# CP_Watsonville_Mid-Model.net
KiCad netlist of a schematic drawn in EAGLE
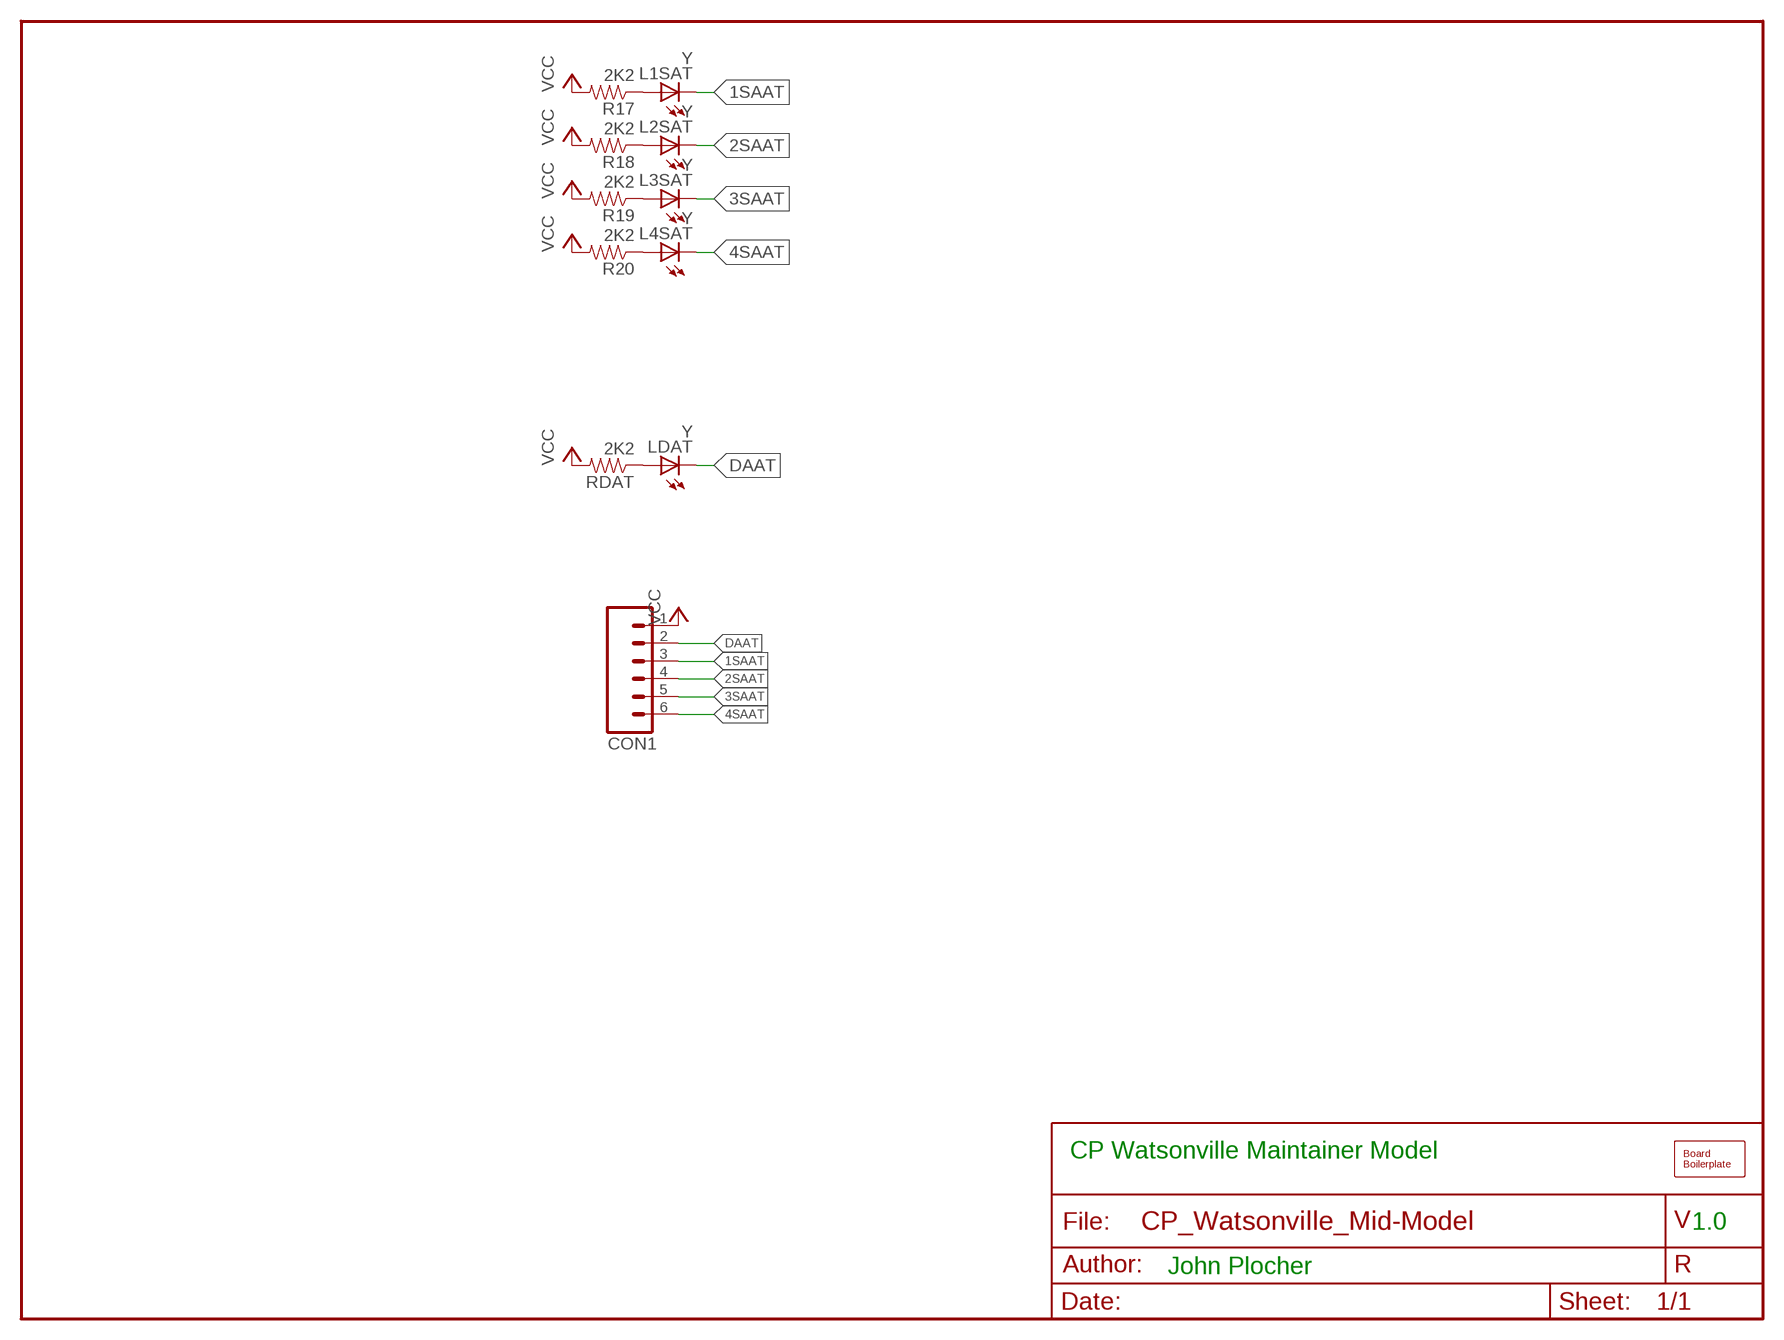
[diagram p0: schematic, sheet 1]

(export (version "E")
  (design (tool "Eeschema 10.0.6"))
  (components
    (comp (ref "BOARD1")
      (value "BOARD100X100")
      (footprint "eagle-import:BOARD-SEEED10X10")
      (libsource (lib "eagle-import") (part "BOARD100X100"))
    )
    (comp (ref "CON1")
      (value "CONNECTOR-M06LOCK")
      (footprint "eagle-import:1X06_LOCK")
      (libsource (lib "eagle-import") (part "CONNECTOR-M06LOCK"))
    )
    (comp (ref "L1SAT")
      (value "Y")
      (footprint "eagle-import:0603-LED")
      (libsource (lib "eagle-import") (part "LED0603-LED"))
    )
    (comp (ref "L2SAT")
      (value "Y")
      (footprint "eagle-import:0603-LED")
      (libsource (lib "eagle-import") (part "LED0603-LED"))
    )
    (comp (ref "L3SAT")
      (value "Y")
      (footprint "eagle-import:0603-LED")
      (libsource (lib "eagle-import") (part "LED0603-LED"))
    )
    (comp (ref "L4SAT")
      (value "Y")
      (footprint "eagle-import:0603-LED")
      (libsource (lib "eagle-import") (part "LED0603-LED"))
    )
    (comp (ref "LDAT")
      (value "Y")
      (footprint "eagle-import:0603-LED")
      (libsource (lib "eagle-import") (part "LED0603-LED"))
    )
    (comp (ref "R17")
      (value "2K2")
      (footprint "eagle-import:0603-RES")
      (libsource (lib "eagle-import") (part "R0603-RES"))
    )
    (comp (ref "R18")
      (value "2K2")
      (footprint "eagle-import:0603-RES")
      (libsource (lib "eagle-import") (part "R0603-RES"))
    )
    (comp (ref "R19")
      (value "2K2")
      (footprint "eagle-import:0603-RES")
      (libsource (lib "eagle-import") (part "R0603-RES"))
    )
    (comp (ref "R20")
      (value "2K2")
      (footprint "eagle-import:0603-RES")
      (libsource (lib "eagle-import") (part "R0603-RES"))
    )
    (comp (ref "RDAT")
      (value "2K2")
      (footprint "eagle-import:0603-RES")
      (libsource (lib "eagle-import") (part "R0603-RES"))
    )
  )
  (nets
    (net (code "1") (name "1SAAT") (class "Default")
      (node (ref "CON1") (pin "3") (pinfunction "3_3") (pintype "passive"))
      (node (ref "L1SAT") (pin "C") (pinfunction "C_C") (pintype "passive"))
    )
    (net (code "2") (name "2SAAT") (class "Default")
      (node (ref "CON1") (pin "4") (pinfunction "4_4") (pintype "passive"))
      (node (ref "L2SAT") (pin "C") (pinfunction "C_C") (pintype "passive"))
    )
    (net (code "3") (name "3SAAT") (class "Default")
      (node (ref "CON1") (pin "5") (pinfunction "5_5") (pintype "passive"))
      (node (ref "L3SAT") (pin "C") (pinfunction "C_C") (pintype "passive"))
    )
    (net (code "4") (name "4SAAT") (class "Default")
      (node (ref "CON1") (pin "6") (pinfunction "6_6") (pintype "passive"))
      (node (ref "L4SAT") (pin "C") (pinfunction "C_C") (pintype "passive"))
    )
    (net (code "5") (name "DAAT") (class "Default")
      (node (ref "CON1") (pin "2") (pinfunction "2_2") (pintype "passive"))
      (node (ref "LDAT") (pin "C") (pinfunction "C_C") (pintype "passive"))
    )
    (net (code "6") (name "Net-(L1SAT-PadA)") (class "Default")
      (node (ref "L1SAT") (pin "A") (pinfunction "A_A") (pintype "passive"))
      (node (ref "R17") (pin "1") (pinfunction "1_1") (pintype "passive"))
    )
    (net (code "7") (name "Net-(L2SAT-PadA)") (class "Default")
      (node (ref "L2SAT") (pin "A") (pinfunction "A_A") (pintype "passive"))
      (node (ref "R18") (pin "1") (pinfunction "1_1") (pintype "passive"))
    )
    (net (code "8") (name "Net-(L3SAT-PadA)") (class "Default")
      (node (ref "L3SAT") (pin "A") (pinfunction "A_A") (pintype "passive"))
      (node (ref "R19") (pin "1") (pinfunction "1_1") (pintype "passive"))
    )
    (net (code "9") (name "Net-(L4SAT-PadA)") (class "Default")
      (node (ref "L4SAT") (pin "A") (pinfunction "A_A") (pintype "passive"))
      (node (ref "R20") (pin "1") (pinfunction "1_1") (pintype "passive"))
    )
    (net (code "10") (name "Net-(LDAT-PadA)") (class "Default")
      (node (ref "LDAT") (pin "A") (pinfunction "A_A") (pintype "passive"))
      (node (ref "RDAT") (pin "1") (pinfunction "1_1") (pintype "passive"))
    )
    (net (code "11") (name "VCC") (class "Default")
      (node (ref "CON1") (pin "1") (pinfunction "1_1") (pintype "passive"))
      (node (ref "R17") (pin "2") (pinfunction "2_2") (pintype "passive"))
      (node (ref "R18") (pin "2") (pinfunction "2_2") (pintype "passive"))
      (node (ref "R19") (pin "2") (pinfunction "2_2") (pintype "passive"))
      (node (ref "R20") (pin "2") (pinfunction "2_2") (pintype "passive"))
      (node (ref "RDAT") (pin "2") (pinfunction "2_2") (pintype "passive"))
    )
  )
)
